# Power_Sheet.net
KiCad netlist of a schematic drawn in Altium Designer
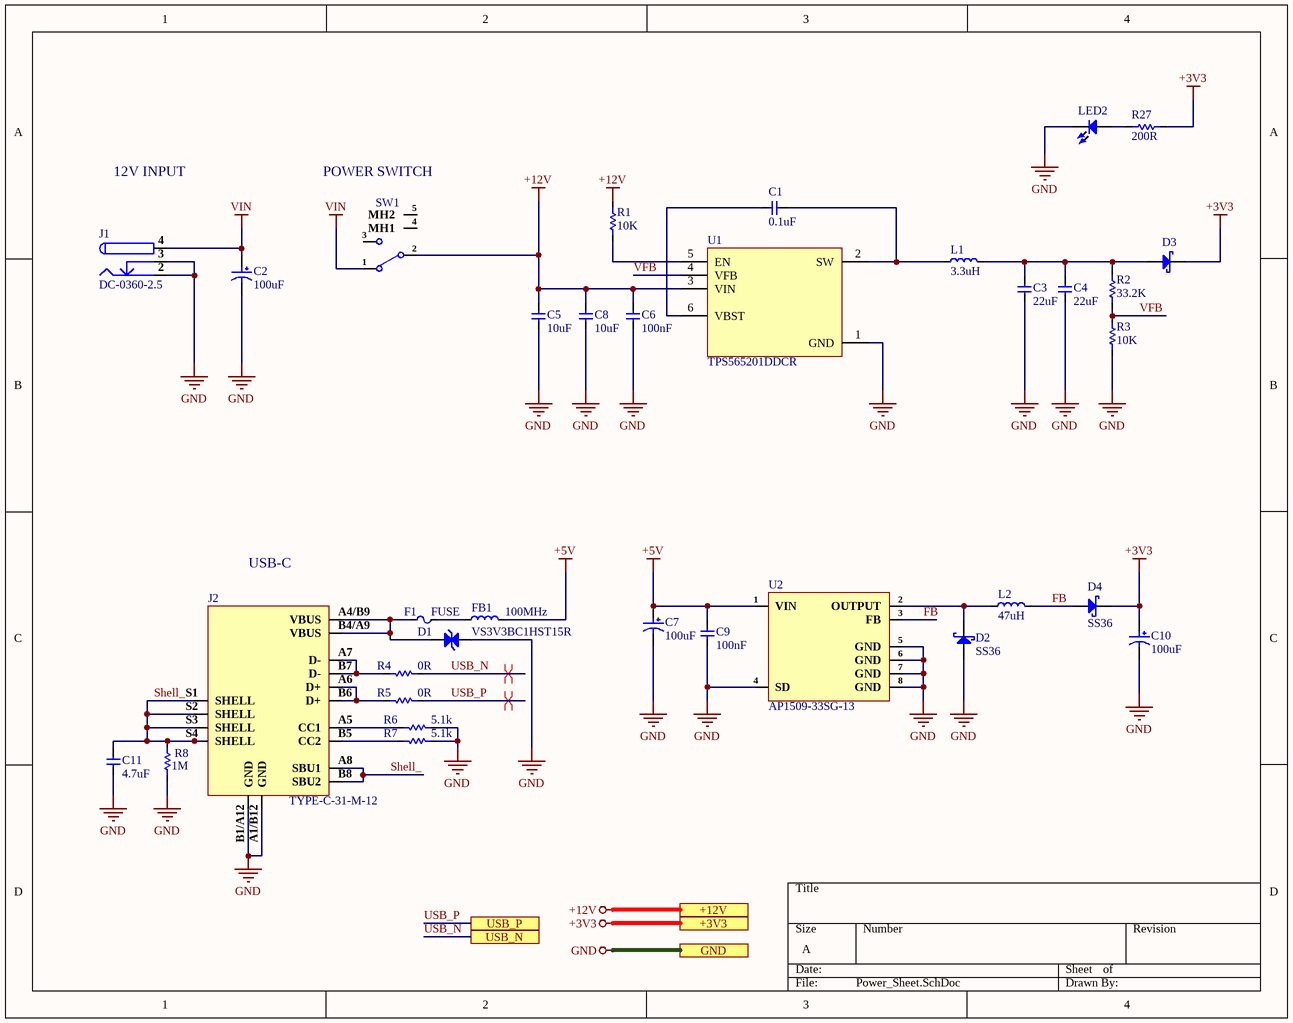
[diagram p0: Power_Sheet.SchDoc]

(export (version "E")
  (design (tool "Eeschema 10.0.6"))
  (components
    (comp (ref "C1")
      (value "0.1uF")
      (footprint "Cap-0603")
      (description "CAP CER 0.1UF 100V X7R 0603")
      (fields
        (field (name "MANUFACTURER") "Yageo")
        (field (name "MANUFACTURER PART NUMBER") "CC0603KRX7R0BB104")
      )
      (libsource (lib "DigitalAzanClock") (part "CC0603KRX7R0BB104"))
    )
    (comp (ref "C2")
      (value "100uF")
      (footprint "RVT1H101M0607")
      (description "100uF 50V ±20% SMD,D6.3xL7.7mm Aluminum Electrolytic Capacitors - SMD ROHS")
      (fields
        (field (name "MANUFACTURER") "ROQANG")
        (field (name "MANUFACTURER PART NUMBER") "RVT1H101M0607")
      )
      (libsource (lib "DigitalAzanClock") (part "RVT1H101M0607"))
    )
    (comp (ref "C3")
      (value "22uF")
      (footprint "Cap-0402")
      (description "CAP CER 22UF 10V X5R 0402")
      (fields
        (field (name "MANUFACTURER") "Murata")
        (field (name "MANUFACTURER PART NUMBER") "GRM158R61A226ME15D")
      )
      (libsource (lib "DigitalAzanClock") (part "GRM158R61A226ME15D"))
    )
    (comp (ref "C4")
      (value "22uF")
      (footprint "Cap-0402")
      (description "CAP CER 22UF 10V X5R 0402")
      (fields
        (field (name "MANUFACTURER") "Murata")
        (field (name "MANUFACTURER PART NUMBER") "GRM158R61A226ME15D")
      )
      (libsource (lib "DigitalAzanClock") (part "GRM158R61A226ME15D"))
    )
    (comp (ref "C5")
      (value "10uF")
      (footprint "Cap-0603")
      (description "10uF 35V X5R 20% Pad SMD 0603")
      (fields
        (field (name "MANUFACTURER") "Murata")
        (field (name "MANUFACTURER PART NUMBER") "GRM188R6YA106MA73D")
      )
      (libsource (lib "DigitalAzanClock") (part "GRM188R6YA106MA73D"))
    )
    (comp (ref "C6")
      (value "100nF")
      (footprint "cap-0402")
      (description "CAP CER 0.1UF 50V X7R 0402")
      (fields
        (field (name "MANUFACTURER") "TDK")
        (field (name "MANUFACTURER PART NUMBER") "C1005X7R1H104KT000F")
      )
      (libsource (lib "DigitalAzanClock") (part "C1005X7R1H104KT000F"))
    )
    (comp (ref "C7")
      (value "100uF")
      (footprint "RVT1H101M0607")
      (description "100uF 50V ±20% SMD,D6.3xL7.7mm Aluminum Electrolytic Capacitors - SMD ROHS")
      (fields
        (field (name "MANUFACTURER") "ROQANG")
        (field (name "MANUFACTURER PART NUMBER") "RVT1H101M0607")
      )
      (libsource (lib "DigitalAzanClock") (part "RVT1H101M0607"))
    )
    (comp (ref "C8")
      (value "10uF")
      (footprint "Cap-0603")
      (description "10uF 35V X5R 20% Pad SMD 0603")
      (fields
        (field (name "MANUFACTURER") "Murata")
        (field (name "MANUFACTURER PART NUMBER") "GRM188R6YA106MA73D")
      )
      (libsource (lib "DigitalAzanClock") (part "GRM188R6YA106MA73D"))
    )
    (comp (ref "C9")
      (value "100nF")
      (footprint "cap-0402")
      (description "CAP CER 0.1UF 50V X7R 0402")
      (fields
        (field (name "MANUFACTURER") "TDK")
        (field (name "MANUFACTURER PART NUMBER") "C1005X7R1H104KT000F")
      )
      (libsource (lib "DigitalAzanClock") (part "C1005X7R1H104KT000F"))
    )
    (comp (ref "C10")
      (value "100uF")
      (footprint "RVT1H101M0607")
      (description "100uF 50V ±20% SMD,D6.3xL7.7mm Aluminum Electrolytic Capacitors - SMD ROHS")
      (fields
        (field (name "MANUFACTURER") "ROQANG")
        (field (name "MANUFACTURER PART NUMBER") "RVT1H101M0607")
      )
      (libsource (lib "DigitalAzanClock") (part "RVT1H101M0607"))
    )
    (comp (ref "C11")
      (value "4.7uF")
      (footprint "Cap-0603")
      (description "50V 4.7nF X7R ±10% 0603 Multilayer Ceramic Capacitors MLCC - SMD/SMT ROHS")
      (fields
        (field (name "MANUFACTURER") "YAGEO")
        (field (name "MANUFACTURER PART NUMBER") "CC0603KRX7R9BB472")
      )
      (libsource (lib "DigitalAzanClock") (part "CC0603KRX7R9BB472"))
    )
    (comp (ref "D1")
      (value "VS3V3BC1HST15R")
      (footprint "VS3V3BC1HST15R")
      (description "8.5V 70W 4V 3.3V SOD-962 Electrostatic and Surge Protection (TVS/ESD) ROHS")
      (fields (field (name "MANUFACTURER") "Rohm Semiconductor"))
      (libsource (lib "DigitalAzanClock") (part "VS3V3BC1HST15R"))
    )
    (comp (ref "D2")
      (value "SS36")
      (footprint "SMA")
      (description "Schottky Barrier Diode SK36, DO-214AB, 3A/60V")
      (fields (field (name "MANUFACTURER") "ON Semiconductor / Fairchild") (field (name "VOLTAGE") "60V"))
      (libsource (lib "DigitalAzanClock") (part "SS36"))
    )
    (comp (ref "D3")
      (value "~")
      (footprint "SMB_")
      (description "DIODE SCHOTTKY 5A 40V SMB")
      (fields (field (name "MANUFACTURER") "Comchip") (field (name "MANUFACTURER PART NUMBER") "SS54B-HF"))
      (libsource (lib "DigitalAzanClock") (part "SS54B-HF"))
    )
    (comp (ref "D4")
      (value "SS36")
      (footprint "SMA")
      (description "Schottky Barrier Diode SK36, DO-214AB, 3A/60V")
      (fields (field (name "MANUFACTURER") "ON Semiconductor / Fairchild") (field (name "VOLTAGE") "60V"))
      (libsource (lib "DigitalAzanClock") (part "SS36"))
    )
    (comp (ref "F1")
      (value "FUSE")
      (footprint "Fuse 1206 (3216 Metric)")
      (description "12V 3A 50A 6A 1206 Resettable Fuses ROHS")
      (fields (field (name "MANUFACTURER") "LUTE") (field (name "MANUFACTURER PART NUMBER") "Manufacturer"))
      (libsource (lib "DigitalAzanClock") (part "1206L300SL12AR"))
    )
    (comp (ref "FB1")
      (value "100MHz")
      (footprint "IND-1206")
      (description "FERRITE BEAD 120 OHM 1206 1LN")
      (fields
        (field (name "MANUFACTURER") "Murata")
        (field (name "MANUFACTURER PART NUMBER") "BLM31PG121SN1L")
      )
      (libsource (lib "DigitalAzanClock") (part "BLM31PG121SN1L"))
    )
    (comp (ref "J1")
      (value "DC-0360-2.5")
      (footprint "DC-0360-2.5")
      (description "DC Power Receptacle 260℃ Brass -20℃~+70℃ 2.5mm 6mm 2.5A 24V Plugin AC/DC Power Connectors ROHS")
      (fields (field (name "MANUFACTURER") "XKB Connectivity") (field (name "LCSC PART NUMBER") "C319122"))
      (libsource (lib "DigitalAzanClock") (part "DC-0360-2.5"))
    )
    (comp (ref "J2")
      (value "TYPE-C-31-M-12")
      (footprint "TYPE-C-31-M-12_")
      (description "250mA 1 16 Female Type-C SMD USB Connectors ROHS")
      (fields
        (field (name "MANUFACTURER") "Korean Hroparts Elec")
        (field (name "LCSC PART NUMBER") "C165948")
      )
      (libsource (lib "DigitalAzanClock") (part "TYPE-C-31-M-12"))
    )
    (comp (ref "L1")
      (value "3.3uH")
      (footprint "FXL0530-3R3-M")
      (description "5.5A 3.3uH Molding Choke ±20% 6A SMD,5.2x5.4mm Power Inductors ROHS")
      (fields
        (field (name "MANUFACTURER") "cjiang (Changjiang Microelectronics Tech)")
        (field (name "MANUFACTURER PART NUMBER") "FXL0530-3R3-M")
      )
      (libsource (lib "DigitalAzanClock") (part "FXL0530-3R3-M"))
    )
    (comp (ref "L2")
      (value "47uH")
      (footprint "SMMS0650-470M")
      (description "2A 47uH Molding Choke ±20% 2.8A SMD,6.6x7.1mm Power Inductors ROHS")
      (fields
        (field (name "MANUFACTURER") "SXN(Shun Xiang Nuo Elec)")
        (field (name "MANUFACTURER PART NUMBER") "SMMS0650-470M")
      )
      (libsource (lib "DigitalAzanClock") (part "SMMS0650-470M"))
    )
    (comp (ref "LED2")
      (value "~")
      (footprint "LED-0603")
      (description "blue 0603 Light Emitting Diodes (LED) ROHS")
      (fields
        (field (name "MANUFACTURER") "Foshan NationStar Optoelectronics")
        (field (name "MANUFACTURER PART NUMBER") "NCD0603B3")
      )
      (libsource (lib "DigitalAzanClock") (part "NCD0603B3"))
    )
    (comp (ref "R1")
      (value "10K")
      (footprint "Res-0603")
      (description "RES SMD 10K OHM 0.1% 1/10W 0603")
      (fields
        (field (name "MANUFACTURER") "Yageo")
        (field (name "MANUFACTURER PART NUMBER") "RT0603BRD0710KL")
      )
      (libsource (lib "DigitalAzanClock") (part "RT0603BRD0710KL"))
    )
    (comp (ref "R2")
      (value "33.2K")
      (footprint "Res-0603")
      (description "RES 33.2K OHM 1% 1/10W 0603")
      (fields
        (field (name "MANUFACTURER") "Yageo")
        (field (name "MANUFACTURER PART NUMBER") "RC0603FR-0733K2L")
      )
      (libsource (lib "DigitalAzanClock") (part "RC0603FR-0733K2L"))
    )
    (comp (ref "R3")
      (value "10K")
      (footprint "Res-0603")
      (description "RES SMD 10K OHM 0.1% 1/10W 0603")
      (fields
        (field (name "MANUFACTURER") "Yageo")
        (field (name "MANUFACTURER PART NUMBER") "RT0603BRD0710KL")
      )
      (libsource (lib "DigitalAzanClock") (part "RT0603BRD0710KL"))
    )
    (comp (ref "R4")
      (value "0R")
      (footprint "Res-0402")
      (description "RES 0 OHM JUMPER 1/16W 0402")
      (fields
        (field (name "MANUFACTURER") "Yageo")
        (field (name "MANUFACTURER PART NUMBER") "RC0402FR-070RL")
      )
      (libsource (lib "DigitalAzanClock") (part "RC0402FR-070RL"))
    )
    (comp (ref "R5")
      (value "0R")
      (footprint "Res-0402")
      (description "RES 0 OHM JUMPER 1/16W 0402")
      (fields
        (field (name "MANUFACTURER") "Yageo")
        (field (name "MANUFACTURER PART NUMBER") "RC0402FR-070RL")
      )
      (libsource (lib "DigitalAzanClock") (part "RC0402FR-070RL"))
    )
    (comp (ref "R6")
      (value "5.1k")
      (footprint "Res-0201")
      (description "RES 5.1K OHM 1% 1/20W 0201")
      (fields
        (field (name "MANUFACTURER") "Yageo")
        (field (name "MANUFACTURER PART NUMBER") "RC0201FR-075K1L")
      )
      (libsource (lib "DigitalAzanClock") (part "RC0201FR-075K1L"))
    )
    (comp (ref "R7")
      (value "5.1k")
      (footprint "Res-0201")
      (description "RES 5.1K OHM 1% 1/20W 0201")
      (fields
        (field (name "MANUFACTURER") "Yageo")
        (field (name "MANUFACTURER PART NUMBER") "RC0201FR-075K1L")
      )
      (libsource (lib "DigitalAzanClock") (part "RC0201FR-075K1L"))
    )
    (comp (ref "R8")
      (value "1M")
      (footprint "Res-0402")
      (description "RES SMD 1M OHM 5% 1/16W 0402")
      (fields
        (field (name "MANUFACTURER") "Yageo")
        (field (name "MANUFACTURER PART NUMBER") "AF0402JR-071ML")
      )
      (libsource (lib "DigitalAzanClock") (part "AF0402JR-071ML"))
    )
    (comp (ref "R27")
      (value "200R")
      (footprint "Res-0402")
      (description "62.5mW Thick Film Resistors 50V ±100ppm/℃ ±1% 200Ω 0402 Chip Resistor - Surface Mount ROHS")
      (fields
        (field (name "MANUFACTURER") "FOJAN")
        (field (name "MANUFACTURER PART NUMBER") "FRC0402F2000TS")
      )
      (libsource (lib "DigitalAzanClock") (part "FRC0402F2000TS"))
    )
    (comp (ref "SW1")
      (value "~")
      (footprint "SS-12D11L5")
      (fields
        (field (name "MANUFACTURER") "XKB Connectivity")
        (field (name "MANUFACTURER PART NUMBER") "SS-12D11L5")
        (field (name "LCSC PART NUMBER") "C319010")
      )
      (libsource (lib "DigitalAzanClock") (part "SS-12D11L5"))
    )
    (comp (ref "U1")
      (value "TPS565201DDCR")
      (footprint "TPS565201DDCR")
      (description "4.5V to 17V, 5A, Synchronous Step-Down Voltage Regulator in SOT23 6-SOT-23-THIN -40 to 125")
      (fields (field (name "MANUFACTURER") "Texas Instruments") (field (name "LCSC PART NUMBER") "C327676"))
      (libsource (lib "DigitalAzanClock") (part "TPS565201DDCR"))
    )
    (comp (ref "U2")
      (value "AP1509-33SG-13")
      (footprint "SOP-8L")
      (description "IC REG BUCK 3.3V 2A 8SOP")
      (fields (field (name "MANUFACTURER") "Diodes") (field (name "LCSC PART NUMBER") "C151823"))
      (libsource (lib "DigitalAzanClock") (part "AP1509-33SG-13"))
    )
  )
  (nets
    (net (code "1") (name "+3V3") (class "Default")
      (node (ref "C10") (pin "1") (pintype "passive"))
      (node (ref "D3") (pin "2") (pinfunction "K_2") (pintype "passive"))
      (node (ref "D4") (pin "1") (pinfunction "K_1") (pintype "passive"))
      (node (ref "R27") (pin "2") (pinfunction "2_2") (pintype "passive"))
    )
    (net (code "2") (name "+5V") (class "Default")
      (node (ref "C7") (pin "1") (pintype "passive"))
      (node (ref "C9") (pin "2") (pinfunction "2_2") (pintype "passive"))
      (node (ref "FB1") (pin "2") (pinfunction "2_2") (pintype "passive"))
      (node (ref "U2") (pin "1") (pinfunction "VIN_1") (pintype "passive"))
    )
    (net (code "3") (name "+12V") (class "Default")
      (node (ref "C5") (pin "2") (pinfunction "2_2") (pintype "passive"))
      (node (ref "C6") (pin "2") (pinfunction "2_2") (pintype "passive"))
      (node (ref "C8") (pin "2") (pinfunction "2_2") (pintype "passive"))
      (node (ref "R1") (pin "2") (pinfunction "2_2") (pintype "passive"))
      (node (ref "SW1") (pin "2") (pinfunction "2_2") (pintype "passive"))
      (node (ref "U1") (pin "3") (pinfunction "VIN_3") (pintype "power_in"))
    )
    (net (code "4") (name "/FB") (class "Default")
      (node (ref "D4") (pin "2") (pinfunction "A_2") (pintype "passive"))
      (node (ref "L2") (pin "2") (pinfunction "2_2") (pintype "passive"))
      (node (ref "U2") (pin "3") (pinfunction "FB_3") (pintype "passive"))
    )
    (net (code "5") (name "/Shell_") (class "Default")
      (node (ref "C11") (pin "2") (pinfunction "2_2") (pintype "passive"))
      (node (ref "J2") (pin "A8") (pinfunction "SBU1_A8") (pintype "passive"))
      (node (ref "J2") (pin "B8") (pinfunction "SBU2_B8") (pintype "passive"))
      (node (ref "J2") (pin "S1") (pinfunction "SHELL_S1") (pintype "passive"))
      (node (ref "J2") (pin "S2") (pinfunction "SHELL_S2") (pintype "passive"))
      (node (ref "J2") (pin "S3") (pinfunction "SHELL_S3") (pintype "passive"))
      (node (ref "J2") (pin "S4") (pinfunction "SHELL_S4") (pintype "passive"))
      (node (ref "R8") (pin "2") (pinfunction "2_2") (pintype "passive"))
    )
    (net (code "6") (name "/USB_N") (class "Default")
      (node (ref "R4") (pin "2") (pinfunction "2_2") (pintype "passive"))
    )
    (net (code "7") (name "/USB_P") (class "Default")
      (node (ref "R5") (pin "2") (pinfunction "2_2") (pintype "passive"))
    )
    (net (code "8") (name "/VFB") (class "Default")
      (node (ref "R2") (pin "1") (pinfunction "1_1") (pintype "passive"))
      (node (ref "R3") (pin "2") (pinfunction "2_2") (pintype "passive"))
      (node (ref "U1") (pin "4") (pinfunction "VFB_4") (pintype "open_emitter"))
    )
    (net (code "9") (name "GND") (class "Default")
      (node (ref "C10") (pin "2") (pintype "passive"))
      (node (ref "C11") (pin "1") (pinfunction "1_1") (pintype "passive"))
      (node (ref "C2") (pin "2") (pintype "passive"))
      (node (ref "C3") (pin "1") (pinfunction "1_1") (pintype "passive"))
      (node (ref "C4") (pin "1") (pinfunction "1_1") (pintype "passive"))
      (node (ref "C5") (pin "1") (pinfunction "1_1") (pintype "passive"))
      (node (ref "C6") (pin "1") (pinfunction "1_1") (pintype "passive"))
      (node (ref "C7") (pin "2") (pintype "passive"))
      (node (ref "C8") (pin "1") (pinfunction "1_1") (pintype "passive"))
      (node (ref "C9") (pin "1") (pinfunction "1_1") (pintype "passive"))
      (node (ref "D1") (pin "2") (pinfunction "A_2") (pintype "passive"))
      (node (ref "D2") (pin "2") (pinfunction "A_2") (pintype "passive"))
      (node (ref "J1") (pin "2") (pinfunction "2_2") (pintype "power_in"))
      (node (ref "J1") (pin "3") (pinfunction "3_3") (pintype "power_in"))
      (node (ref "J2") (pin "A1/B12") (pinfunction "GND_A1/B12") (pintype "power_in"))
      (node (ref "J2") (pin "B1/A12") (pinfunction "GND_B1/A12") (pintype "power_in"))
      (node (ref "LED2") (pin "2") (pinfunction "2_2") (pintype "passive"))
      (node (ref "R3") (pin "1") (pinfunction "1_1") (pintype "passive"))
      (node (ref "R6") (pin "1") (pinfunction "1_1") (pintype "passive"))
      (node (ref "R7") (pin "1") (pinfunction "1_1") (pintype "passive"))
      (node (ref "R8") (pin "1") (pinfunction "1_1") (pintype "passive"))
      (node (ref "U1") (pin "1") (pinfunction "GND_1") (pintype "power_in"))
      (node (ref "U2") (pin "4") (pinfunction "SD_4") (pintype "passive"))
      (node (ref "U2") (pin "5") (pinfunction "GND_5") (pintype "passive"))
      (node (ref "U2") (pin "6") (pinfunction "GND_6") (pintype "passive"))
      (node (ref "U2") (pin "7") (pinfunction "GND_7") (pintype "passive"))
      (node (ref "U2") (pin "8") (pinfunction "GND_8") (pintype "passive"))
    )
    (net (code "10") (name "Net-(D1-A-Pad1)") (class "Default")
      (node (ref "D1") (pin "1") (pinfunction "A_1") (pintype "passive"))
      (node (ref "F1") (pin "1") (pinfunction "1_1") (pintype "passive"))
      (node (ref "J2") (pin "A4/B9") (pinfunction "VBUS_A4/B9") (pintype "power_in"))
      (node (ref "J2") (pin "B4/A9") (pinfunction "VBUS_B4/A9") (pintype "power_in"))
    )
    (net (code "11") (name "Net-(D2-K)") (class "Default")
      (node (ref "D2") (pin "1") (pinfunction "K_1") (pintype "passive"))
      (node (ref "L2") (pin "1") (pinfunction "1_1") (pintype "passive"))
      (node (ref "U2") (pin "2") (pinfunction "OUTPUT_2") (pintype "passive"))
    )
    (net (code "12") (name "Net-(D3-A)") (class "Default")
      (node (ref "C3") (pin "2") (pinfunction "2_2") (pintype "passive"))
      (node (ref "C4") (pin "2") (pinfunction "2_2") (pintype "passive"))
      (node (ref "D3") (pin "1") (pinfunction "A_1") (pintype "passive"))
      (node (ref "L1") (pin "2") (pinfunction "2_2") (pintype "passive"))
      (node (ref "R2") (pin "2") (pinfunction "2_2") (pintype "passive"))
    )
    (net (code "13") (name "Net-(F1-Pad2)") (class "Default")
      (node (ref "F1") (pin "2") (pinfunction "2_2") (pintype "passive"))
      (node (ref "FB1") (pin "1") (pinfunction "1_1") (pintype "passive"))
    )
    (net (code "14") (name "Net-(J2-CC1)") (class "Default")
      (node (ref "J2") (pin "A5") (pinfunction "CC1_A5") (pintype "passive"))
      (node (ref "R6") (pin "2") (pinfunction "2_2") (pintype "passive"))
    )
    (net (code "15") (name "Net-(J2-CC2)") (class "Default")
      (node (ref "J2") (pin "B5") (pinfunction "CC2_B5") (pintype "passive"))
      (node (ref "R7") (pin "2") (pinfunction "2_2") (pintype "passive"))
    )
    (net (code "16") (name "Net-(J2-D+-PadA6)") (class "Default")
      (node (ref "J2") (pin "A6") (pinfunction "D+_A6") (pintype "passive"))
      (node (ref "J2") (pin "B6") (pinfunction "D+_B6") (pintype "passive"))
      (node (ref "R5") (pin "1") (pinfunction "1_1") (pintype "passive"))
    )
    (net (code "17") (name "Net-(J2-D--PadA7)") (class "Default")
      (node (ref "J2") (pin "A7") (pinfunction "D-_A7") (pintype "passive"))
      (node (ref "J2") (pin "B7") (pinfunction "D-_B7") (pintype "passive"))
      (node (ref "R4") (pin "1") (pinfunction "1_1") (pintype "passive"))
    )
    (net (code "18") (name "Net-(LED2-Pad1)") (class "Default")
      (node (ref "LED2") (pin "1") (pinfunction "1_1") (pintype "passive"))
      (node (ref "R27") (pin "1") (pinfunction "1_1") (pintype "passive"))
    )
    (net (code "19") (name "Net-(U1-EN)") (class "Default")
      (node (ref "R1") (pin "1") (pinfunction "1_1") (pintype "passive"))
      (node (ref "U1") (pin "5") (pinfunction "EN_5") (pintype "open_emitter"))
    )
    (net (code "20") (name "Net-(U1-SW)") (class "Default")
      (node (ref "C1") (pin "2") (pinfunction "2_2") (pintype "passive"))
      (node (ref "L1") (pin "1") (pinfunction "1_1") (pintype "passive"))
      (node (ref "U1") (pin "2") (pinfunction "SW_2") (pintype "power_in"))
    )
    (net (code "21") (name "Net-(U1-VBST)") (class "Default")
      (node (ref "C1") (pin "1") (pinfunction "1_1") (pintype "passive"))
      (node (ref "U1") (pin "6") (pinfunction "VBST_6") (pintype "open_emitter"))
    )
    (net (code "22") (name "VIN") (class "Default")
      (node (ref "C2") (pin "1") (pintype "passive"))
      (node (ref "J1") (pin "4") (pinfunction "4_4") (pintype "power_in"))
      (node (ref "SW1") (pin "1") (pinfunction "1_1") (pintype "passive"))
    )
    (net (code "23") (name "unconnected-(SW1-MH1-Pad4)") (class "Default")
      (node (ref "SW1") (pin "4") (pinfunction "MH1_4") (pintype "passive"))
    )
    (net (code "24") (name "unconnected-(SW1-MH2-Pad5)") (class "Default")
      (node (ref "SW1") (pin "5") (pinfunction "MH2_5") (pintype "passive"))
    )
    (net (code "25") (name "unconnected-(SW1-Pad3)") (class "Default")
      (node (ref "SW1") (pin "3") (pinfunction "3_3") (pintype "passive"))
    )
  )
)
